# STM32.net
KiCad netlist of a schematic drawn in Altium Designer
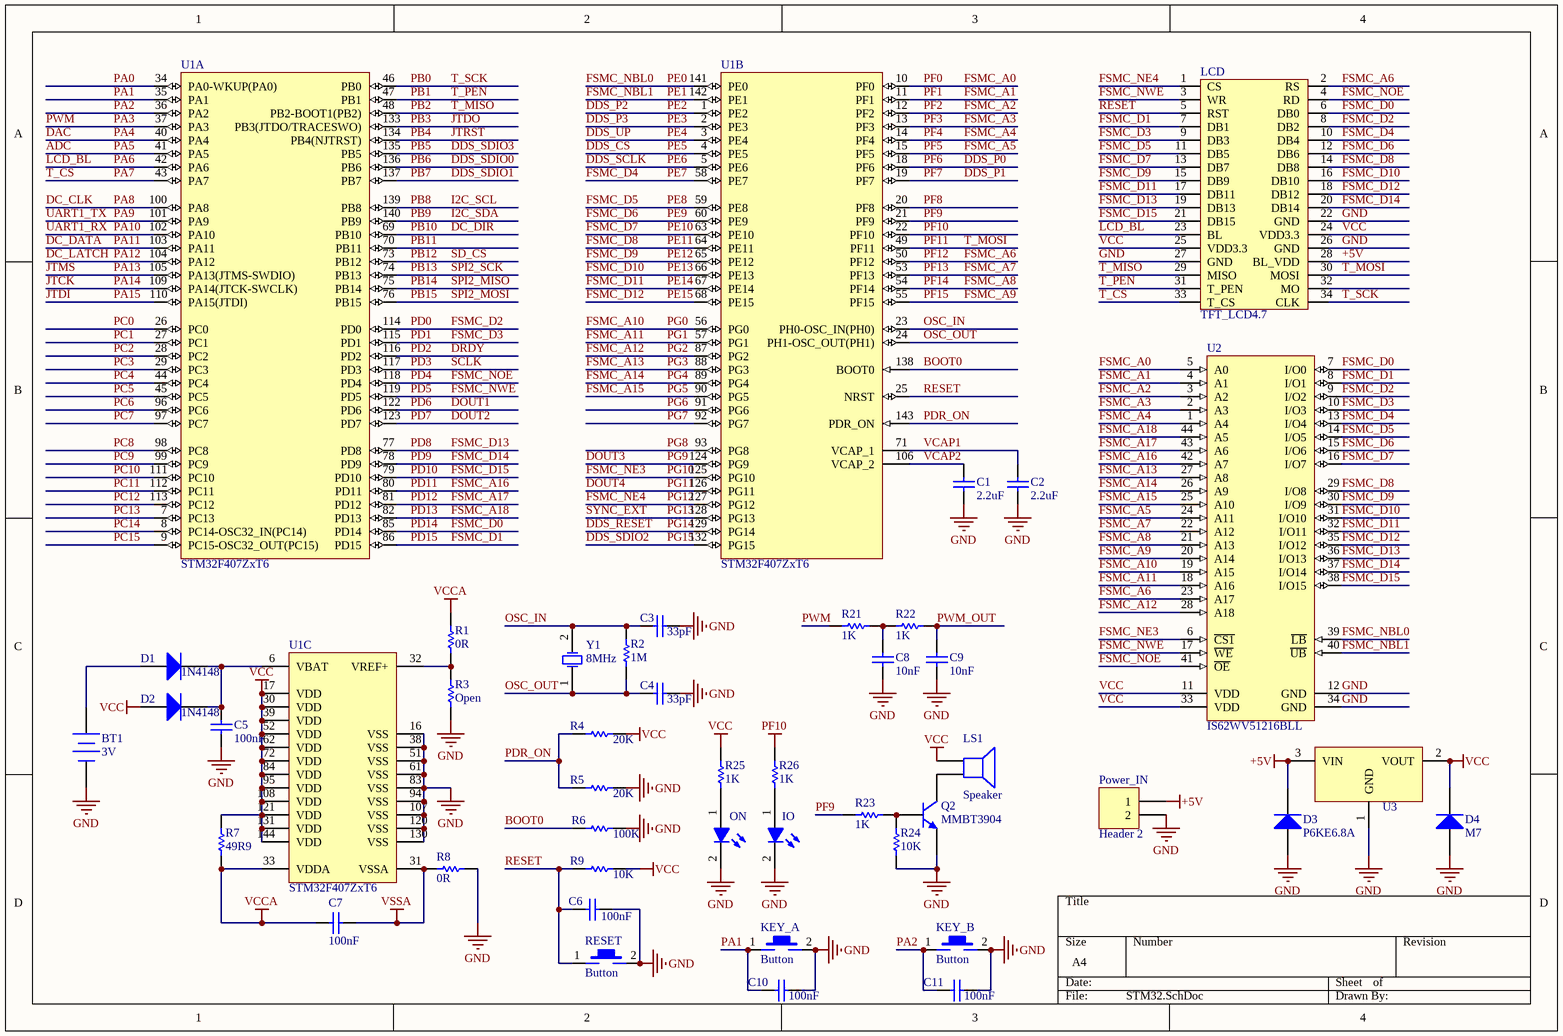
[diagram p0: STM32.SchDoc]

(export (version "E")
  (design (tool "Eeschema 10.0.6"))
  (components
    (comp (ref "BT1")
      (value "3V")
      (footprint "BAT-2")
      (description "Multicell Battery")
      (fields (field (name "PUBLISHER") "Altium Limited"))
      (libsource (lib "Miscellaneous Devices") (part "Battery"))
    )
    (comp (ref "C1")
      (value "2.2uF")
      (footprint "CAPC0603(1608)55_M")
      (libsource (lib "Slivy's ibrary") (part "CAP"))
    )
    (comp (ref "C2")
      (value "2.2uF")
      (footprint "CAPC0603(1608)55_M")
      (libsource (lib "Slivy's ibrary") (part "CAP"))
    )
    (comp (ref "C3")
      (value "33pF")
      (footprint "CAPC0603(1608)55_M")
      (libsource (lib "Slivy's ibrary") (part "CAP"))
    )
    (comp (ref "C4")
      (value "33pF")
      (footprint "CAPC0603(1608)55_M")
      (libsource (lib "Slivy's ibrary") (part "CAP"))
    )
    (comp (ref "C5")
      (value "100nF")
      (footprint "CAPC0603(1608)55_M")
      (libsource (lib "Slivy's ibrary") (part "CAP"))
    )
    (comp (ref "C6")
      (value "100nF")
      (footprint "CAPC0603(1608)55_M")
      (libsource (lib "Slivy's ibrary") (part "CAP"))
    )
    (comp (ref "C7")
      (value "100nF")
      (footprint "CAPC0603(1608)55_M")
      (libsource (lib "Slivy's ibrary") (part "CAP"))
    )
    (comp (ref "C8")
      (value "10nF")
      (footprint "CAPC0603(1608)55_M")
      (libsource (lib "Slivy's ibrary") (part "CAP"))
    )
    (comp (ref "C9")
      (value "10nF")
      (footprint "CAPC0603(1608)55_M")
      (libsource (lib "Slivy's ibrary") (part "CAP"))
    )
    (comp (ref "C10")
      (value "100nF")
      (footprint "CAPC0603(1608)55_M")
      (libsource (lib "Slivy's ibrary") (part "CAP"))
    )
    (comp (ref "C11")
      (value "100nF")
      (footprint "CAPC0603(1608)55_M")
      (libsource (lib "Slivy's ibrary") (part "CAP"))
    )
    (comp (ref "D1") (value "1N4148") (footprint "LL34") (libsource (lib "Slivy's ibrary") (part "Diode")))
    (comp (ref "D2") (value "1N4148") (footprint "LL34") (libsource (lib "Slivy's ibrary") (part "Diode")))
    (comp (ref "D3")
      (value "P6KE6.8A")
      (footprint "DO-214AC")
      (libsource (lib "Slivy's ibrary") (part "Diode"))
    )
    (comp (ref "D4") (value "M7") (footprint "DO-214AC") (libsource (lib "Slivy's ibrary") (part "Diode")))
    (comp (ref "IO")
      (value "LED-BLUE")
      (footprint "0603LED_BLUE_V")
      (libsource (lib "Slivy's ibrary") (part "LED-BLUE"))
    )
    (comp (ref "KEY_A")
      (value "Button")
      (footprint "Button665")
      (libsource (lib "Slivy's ibrary") (part "Button"))
    )
    (comp (ref "KEY_B")
      (value "Button")
      (footprint "Button665")
      (libsource (lib "Slivy's ibrary") (part "Button"))
    )
    (comp (ref "LCD")
      (value "TFT_LCD4.7")
      (footprint "DB2*17-3.5")
      (libsource (lib "Slivy's ibrary") (part "TFT_LCD4.7"))
    )
    (comp (ref "LS1")
      (value "Speaker")
      (footprint "Buzzer")
      (description "Loudspeaker")
      (fields (field (name "PUBLISHER") "Altium Limited"))
      (libsource (lib "Miscellaneous Devices") (part "Speaker"))
    )
    (comp (ref "ON")
      (value "LED-BLUE")
      (footprint "0603LED_BLUE_V")
      (libsource (lib "Slivy's ibrary") (part "LED-BLUE"))
    )
    (comp (ref "Power_IN")
      (value "Header 2")
      (footprint "VH3.96-2-AW")
      (description "Header, 2-Pin")
      (fields (field (name "PUBLISHER") "Altium Limited"))
      (libsource (lib "Miscellaneous Connectors") (part "Header 2"))
    )
    (comp (ref "Q2")
      (value "MMBT3904")
      (footprint "SOT23_M")
      (description "NPN General Purpose Amplifier")
      (fields (field (name "PUBLISHER") "Altium Limited"))
      (libsource (lib "Slivy's ibrary") (part "MMBT3904"))
    )
    (comp (ref "R1")
      (value "0R")
      (footprint "RESC0603(1608)_M")
      (libsource (lib "Slivy's ibrary") (part "RES"))
    )
    (comp (ref "R2")
      (value "1M")
      (footprint "RESC0603(1608)_M")
      (libsource (lib "Slivy's ibrary") (part "RES"))
    )
    (comp (ref "R3")
      (value "Open")
      (footprint "RESC0603(1608)_M")
      (libsource (lib "Slivy's ibrary") (part "RES"))
    )
    (comp (ref "R4")
      (value "20K")
      (footprint "RESC0603(1608)_M")
      (libsource (lib "Slivy's ibrary") (part "RES"))
    )
    (comp (ref "R5")
      (value "20K")
      (footprint "RESC0603(1608)_M")
      (libsource (lib "Slivy's ibrary") (part "RES"))
    )
    (comp (ref "R6")
      (value "100K")
      (footprint "RESC0603(1608)_M")
      (libsource (lib "Slivy's ibrary") (part "RES"))
    )
    (comp (ref "R7")
      (value "49R9")
      (footprint "RESC0603(1608)_M")
      (libsource (lib "Slivy's ibrary") (part "RES"))
    )
    (comp (ref "R8")
      (value "0R")
      (footprint "RESC0603(1608)_M")
      (libsource (lib "Slivy's ibrary") (part "RES"))
    )
    (comp (ref "R9")
      (value "10K")
      (footprint "RESC0603(1608)_M")
      (libsource (lib "Slivy's ibrary") (part "RES"))
    )
    (comp (ref "R21")
      (value "1K")
      (footprint "RESC0603(1608)_M")
      (libsource (lib "Slivy's ibrary") (part "RES"))
    )
    (comp (ref "R22")
      (value "1K")
      (footprint "RESC0603(1608)_M")
      (libsource (lib "Slivy's ibrary") (part "RES"))
    )
    (comp (ref "R23")
      (value "1K")
      (footprint "RESC0603(1608)_M")
      (libsource (lib "Slivy's ibrary") (part "RES"))
    )
    (comp (ref "R24")
      (value "10K")
      (footprint "RESC0603(1608)_M")
      (libsource (lib "Slivy's ibrary") (part "RES"))
    )
    (comp (ref "R25")
      (value "1K")
      (footprint "RESC0603(1608)_M")
      (libsource (lib "Slivy's ibrary") (part "RES"))
    )
    (comp (ref "R26")
      (value "1K")
      (footprint "RESC0603(1608)_M")
      (libsource (lib "Slivy's ibrary") (part "RES"))
    )
    (comp (ref "RESET")
      (value "Button")
      (footprint "Button665")
      (libsource (lib "Slivy's ibrary") (part "Button"))
    )
    (comp (ref "U1")
      (value "STM32F407ZxT6")
      (footprint "LQFP144")
      (libsource (lib "Slivy's ibrary") (part "STM32F407ZxT6"))
    )
    (comp (ref "U2")
      (value "IS62WV51216BLL")
      (footprint "TSOP-2-44")
      (libsource (lib "Slivy's ibrary") (part "IS62WV51216BLL"))
    )
    (comp (ref "U3")
      (value "AMS1117")
      (footprint "SOT-223_M")
      (libsource (lib "Slivy's ibrary") (part "AMS1117"))
    )
    (comp (ref "Y1")
      (value "8MHz")
      (footprint "HC-49S")
      (description "Crystal Oscillator")
      (fields (field (name "PUBLISHER") "Altium Limited"))
      (libsource (lib "Slivy's ibrary") (part "XTAL"))
    )
  )
  (nets
    (net (code "1") (name "+5V") (class "Default")
      (node (ref "D3") (pin "1") (pinfunction "K_1") (pintype "passive"))
      (node (ref "LCD") (pin "28") (pinfunction "BL_VDD_28") (pintype "passive"))
      (node (ref "Power_IN") (pin "1") (pinfunction "1_1") (pintype "passive"))
      (node (ref "U3") (pin "3") (pinfunction "VIN_3") (pintype "power_in"))
    )
    (net (code "2") (name "/ADC") (class "Default")
      (node (ref "U1") (pin "41") (pinfunction "PA5_41") (pintype "bidirectional"))
    )
    (net (code "3") (name "/BOOT0") (class "Default")
      (node (ref "R6") (pin "1") (pinfunction "1_1") (pintype "passive"))
      (node (ref "U1") (pin "138") (pinfunction "BOOT0_138") (pintype "input"))
    )
    (net (code "4") (name "/DAC") (class "Default")
      (node (ref "U1") (pin "40") (pinfunction "PA4_40") (pintype "bidirectional"))
    )
    (net (code "5") (name "/DC_CLK") (class "Default")
      (node (ref "U1") (pin "100") (pinfunction "PA8_100") (pintype "bidirectional"))
    )
    (net (code "6") (name "/DC_DATA") (class "Default")
      (node (ref "U1") (pin "103") (pinfunction "PA11_103") (pintype "bidirectional"))
    )
    (net (code "7") (name "/DC_DIR") (class "Default")
      (node (ref "U1") (pin "69") (pinfunction "PB10_69") (pintype "bidirectional"))
    )
    (net (code "8") (name "/DC_LATCH") (class "Default")
      (node (ref "U1") (pin "104") (pinfunction "PA12_104") (pintype "bidirectional"))
    )
    (net (code "9") (name "/DDS_CS") (class "Default")
      (node (ref "U1") (pin "4") (pinfunction "PE5_4") (pintype "bidirectional"))
    )
    (net (code "10") (name "/DDS_P0") (class "Default")
      (node (ref "U1") (pin "18") (pinfunction "PF6_18") (pintype "bidirectional"))
    )
    (net (code "11") (name "/DDS_P1") (class "Default")
      (node (ref "U1") (pin "19") (pinfunction "PF7_19") (pintype "bidirectional"))
    )
    (net (code "12") (name "/DDS_P2") (class "Default")
      (node (ref "U1") (pin "1") (pinfunction "PE2_1") (pintype "bidirectional"))
    )
    (net (code "13") (name "/DDS_P3") (class "Default")
      (node (ref "U1") (pin "2") (pinfunction "PE3_2") (pintype "bidirectional"))
    )
    (net (code "14") (name "/DDS_RESET") (class "Default")
      (node (ref "U1") (pin "129") (pinfunction "PG14_129") (pintype "bidirectional"))
    )
    (net (code "15") (name "/DDS_SCLK") (class "Default")
      (node (ref "U1") (pin "5") (pinfunction "PE6_5") (pintype "bidirectional"))
    )
    (net (code "16") (name "/DDS_SDIO0") (class "Default")
      (node (ref "U1") (pin "136") (pinfunction "PB6_136") (pintype "bidirectional"))
    )
    (net (code "17") (name "/DDS_SDIO1") (class "Default")
      (node (ref "U1") (pin "137") (pinfunction "PB7_137") (pintype "bidirectional"))
    )
    (net (code "18") (name "/DDS_SDIO2") (class "Default")
      (node (ref "U1") (pin "132") (pinfunction "PG15_132") (pintype "bidirectional"))
    )
    (net (code "19") (name "/DDS_SDIO3") (class "Default")
      (node (ref "U1") (pin "135") (pinfunction "PB5_135") (pintype "bidirectional"))
    )
    (net (code "20") (name "/DDS_UP") (class "Default")
      (node (ref "U1") (pin "3") (pinfunction "PE4_3") (pintype "bidirectional"))
    )
    (net (code "21") (name "/DOUT1") (class "Default")
      (node (ref "U1") (pin "122") (pinfunction "PD6_122") (pintype "bidirectional"))
    )
    (net (code "22") (name "/DOUT2") (class "Default")
      (node (ref "U1") (pin "123") (pinfunction "PD7_123") (pintype "bidirectional"))
    )
    (net (code "23") (name "/DOUT3") (class "Default")
      (node (ref "U1") (pin "124") (pinfunction "PG9_124") (pintype "bidirectional"))
    )
    (net (code "24") (name "/DOUT4") (class "Default")
      (node (ref "U1") (pin "126") (pinfunction "PG11_126") (pintype "bidirectional"))
    )
    (net (code "25") (name "/DRDY") (class "Default")
      (node (ref "U1") (pin "116") (pinfunction "PD2_116") (pintype "bidirectional"))
    )
    (net (code "26") (name "/FSMC_A0") (class "Default")
      (node (ref "U1") (pin "10") (pinfunction "PF0_10") (pintype "bidirectional"))
      (node (ref "U2") (pin "5") (pinfunction "A0_5") (pintype "input"))
    )
    (net (code "27") (name "/FSMC_A1") (class "Default")
      (node (ref "U1") (pin "11") (pinfunction "PF1_11") (pintype "bidirectional"))
      (node (ref "U2") (pin "4") (pinfunction "A1_4") (pintype "input"))
    )
    (net (code "28") (name "/FSMC_A2") (class "Default")
      (node (ref "U1") (pin "12") (pinfunction "PF2_12") (pintype "bidirectional"))
      (node (ref "U2") (pin "3") (pinfunction "A2_3") (pintype "input"))
    )
    (net (code "29") (name "/FSMC_A3") (class "Default")
      (node (ref "U1") (pin "13") (pinfunction "PF3_13") (pintype "bidirectional"))
      (node (ref "U2") (pin "2") (pinfunction "A3_2") (pintype "input"))
    )
    (net (code "30") (name "/FSMC_A4") (class "Default")
      (node (ref "U1") (pin "14") (pinfunction "PF4_14") (pintype "bidirectional"))
      (node (ref "U2") (pin "1") (pinfunction "A4_1") (pintype "input"))
    )
    (net (code "31") (name "/FSMC_A5") (class "Default")
      (node (ref "U1") (pin "15") (pinfunction "PF5_15") (pintype "bidirectional"))
      (node (ref "U2") (pin "24") (pinfunction "A11_24") (pintype "input"))
    )
    (net (code "32") (name "/FSMC_A6") (class "Default")
      (node (ref "LCD") (pin "2") (pinfunction "RS_2") (pintype "passive"))
      (node (ref "U1") (pin "50") (pinfunction "PF12_50") (pintype "bidirectional"))
      (node (ref "U2") (pin "23") (pinfunction "A17_23") (pintype "input"))
    )
    (net (code "33") (name "/FSMC_A7") (class "Default")
      (node (ref "U1") (pin "53") (pinfunction "PF13_53") (pintype "bidirectional"))
      (node (ref "U2") (pin "22") (pinfunction "A12_22") (pintype "input"))
    )
    (net (code "34") (name "/FSMC_A8") (class "Default")
      (node (ref "U1") (pin "54") (pinfunction "PF14_54") (pintype "bidirectional"))
      (node (ref "U2") (pin "21") (pinfunction "A13_21") (pintype "input"))
    )
    (net (code "35") (name "/FSMC_A9") (class "Default")
      (node (ref "U1") (pin "55") (pinfunction "PF15_55") (pintype "bidirectional"))
      (node (ref "U2") (pin "20") (pinfunction "A14_20") (pintype "input"))
    )
    (net (code "36") (name "/FSMC_A10") (class "Default")
      (node (ref "U1") (pin "56") (pinfunction "PG0_56") (pintype "bidirectional"))
      (node (ref "U2") (pin "19") (pinfunction "A15_19") (pintype "input"))
    )
    (net (code "37") (name "/FSMC_A11") (class "Default")
      (node (ref "U1") (pin "57") (pinfunction "PG1_57") (pintype "bidirectional"))
      (node (ref "U2") (pin "18") (pinfunction "A16_18") (pintype "input"))
    )
    (net (code "38") (name "/FSMC_A12") (class "Default")
      (node (ref "U1") (pin "87") (pinfunction "PG2_87") (pintype "bidirectional"))
      (node (ref "U2") (pin "28") (pinfunction "A18_28") (pintype "input"))
    )
    (net (code "39") (name "/FSMC_A13") (class "Default")
      (node (ref "U1") (pin "88") (pinfunction "PG3_88") (pintype "bidirectional"))
      (node (ref "U2") (pin "27") (pinfunction "A8_27") (pintype "input"))
    )
    (net (code "40") (name "/FSMC_A14") (class "Default")
      (node (ref "U1") (pin "89") (pinfunction "PG4_89") (pintype "bidirectional"))
      (node (ref "U2") (pin "26") (pinfunction "A9_26") (pintype "input"))
    )
    (net (code "41") (name "/FSMC_A15") (class "Default")
      (node (ref "U1") (pin "90") (pinfunction "PG5_90") (pintype "bidirectional"))
      (node (ref "U2") (pin "25") (pinfunction "A10_25") (pintype "input"))
    )
    (net (code "42") (name "/FSMC_A16") (class "Default")
      (node (ref "U1") (pin "80") (pinfunction "PD11_80") (pintype "bidirectional"))
      (node (ref "U2") (pin "42") (pinfunction "A7_42") (pintype "input"))
    )
    (net (code "43") (name "/FSMC_A17") (class "Default")
      (node (ref "U1") (pin "81") (pinfunction "PD12_81") (pintype "bidirectional"))
      (node (ref "U2") (pin "43") (pinfunction "A6_43") (pintype "input"))
    )
    (net (code "44") (name "/FSMC_A18") (class "Default")
      (node (ref "U1") (pin "82") (pinfunction "PD13_82") (pintype "bidirectional"))
      (node (ref "U2") (pin "44") (pinfunction "A5_44") (pintype "input"))
    )
    (net (code "45") (name "/FSMC_D0") (class "Default")
      (node (ref "LCD") (pin "6") (pinfunction "DB0_6") (pintype "passive"))
      (node (ref "U1") (pin "85") (pinfunction "PD14_85") (pintype "bidirectional"))
      (node (ref "U2") (pin "7") (pinfunction "I/O0_7") (pintype "bidirectional"))
    )
    (net (code "46") (name "/FSMC_D1") (class "Default")
      (node (ref "LCD") (pin "7") (pinfunction "DB1_7") (pintype "passive"))
      (node (ref "U1") (pin "86") (pinfunction "PD15_86") (pintype "bidirectional"))
      (node (ref "U2") (pin "8") (pinfunction "I/O1_8") (pintype "bidirectional"))
    )
    (net (code "47") (name "/FSMC_D2") (class "Default")
      (node (ref "LCD") (pin "8") (pinfunction "DB2_8") (pintype "passive"))
      (node (ref "U1") (pin "114") (pinfunction "PD0_114") (pintype "bidirectional"))
      (node (ref "U2") (pin "9") (pinfunction "I/O2_9") (pintype "bidirectional"))
    )
    (net (code "48") (name "/FSMC_D3") (class "Default")
      (node (ref "LCD") (pin "9") (pinfunction "DB3_9") (pintype "passive"))
      (node (ref "U1") (pin "115") (pinfunction "PD1_115") (pintype "bidirectional"))
      (node (ref "U2") (pin "10") (pinfunction "I/O3_10") (pintype "bidirectional"))
    )
    (net (code "49") (name "/FSMC_D4") (class "Default")
      (node (ref "LCD") (pin "10") (pinfunction "DB4_10") (pintype "passive"))
      (node (ref "U1") (pin "58") (pinfunction "PE7_58") (pintype "bidirectional"))
      (node (ref "U2") (pin "13") (pinfunction "I/O4_13") (pintype "bidirectional"))
    )
    (net (code "50") (name "/FSMC_D5") (class "Default")
      (node (ref "LCD") (pin "11") (pinfunction "DB5_11") (pintype "passive"))
      (node (ref "U1") (pin "59") (pinfunction "PE8_59") (pintype "bidirectional"))
      (node (ref "U2") (pin "14") (pinfunction "I/O5_14") (pintype "bidirectional"))
    )
    (net (code "51") (name "/FSMC_D6") (class "Default")
      (node (ref "LCD") (pin "12") (pinfunction "DB6_12") (pintype "passive"))
      (node (ref "U1") (pin "60") (pinfunction "PE9_60") (pintype "bidirectional"))
      (node (ref "U2") (pin "15") (pinfunction "I/O6_15") (pintype "bidirectional"))
    )
    (net (code "52") (name "/FSMC_D7") (class "Default")
      (node (ref "LCD") (pin "13") (pinfunction "DB7_13") (pintype "passive"))
      (node (ref "U1") (pin "63") (pinfunction "PE10_63") (pintype "bidirectional"))
      (node (ref "U2") (pin "16") (pinfunction "I/O7_16") (pintype "bidirectional"))
    )
    (net (code "53") (name "/FSMC_D8") (class "Default")
      (node (ref "LCD") (pin "14") (pinfunction "DB8_14") (pintype "passive"))
      (node (ref "U1") (pin "64") (pinfunction "PE11_64") (pintype "bidirectional"))
      (node (ref "U2") (pin "29") (pinfunction "I/O8_29") (pintype "bidirectional"))
    )
    (net (code "54") (name "/FSMC_D9") (class "Default")
      (node (ref "LCD") (pin "15") (pinfunction "DB9_15") (pintype "passive"))
      (node (ref "U1") (pin "65") (pinfunction "PE12_65") (pintype "bidirectional"))
      (node (ref "U2") (pin "30") (pinfunction "I/O9_30") (pintype "bidirectional"))
    )
    (net (code "55") (name "/FSMC_D10") (class "Default")
      (node (ref "LCD") (pin "16") (pinfunction "DB10_16") (pintype "passive"))
      (node (ref "U1") (pin "66") (pinfunction "PE13_66") (pintype "bidirectional"))
      (node (ref "U2") (pin "31") (pinfunction "I/O10_31") (pintype "bidirectional"))
    )
    (net (code "56") (name "/FSMC_D11") (class "Default")
      (node (ref "LCD") (pin "17") (pinfunction "DB11_17") (pintype "passive"))
      (node (ref "U1") (pin "67") (pinfunction "PE14_67") (pintype "bidirectional"))
      (node (ref "U2") (pin "32") (pinfunction "I/O11_32") (pintype "bidirectional"))
    )
    (net (code "57") (name "/FSMC_D12") (class "Default")
      (node (ref "LCD") (pin "18") (pinfunction "DB12_18") (pintype "passive"))
      (node (ref "U1") (pin "68") (pinfunction "PE15_68") (pintype "bidirectional"))
      (node (ref "U2") (pin "35") (pinfunction "I/O12_35") (pintype "bidirectional"))
    )
    (net (code "58") (name "/FSMC_D13") (class "Default")
      (node (ref "LCD") (pin "19") (pinfunction "DB13_19") (pintype "passive"))
      (node (ref "U1") (pin "77") (pinfunction "PD8_77") (pintype "bidirectional"))
      (node (ref "U2") (pin "36") (pinfunction "I/O13_36") (pintype "bidirectional"))
    )
    (net (code "59") (name "/FSMC_D14") (class "Default")
      (node (ref "LCD") (pin "20") (pinfunction "DB14_20") (pintype "passive"))
      (node (ref "U1") (pin "78") (pinfunction "PD9_78") (pintype "bidirectional"))
      (node (ref "U2") (pin "37") (pinfunction "I/O14_37") (pintype "bidirectional"))
    )
    (net (code "60") (name "/FSMC_D15") (class "Default")
      (node (ref "LCD") (pin "21") (pinfunction "DB15_21") (pintype "passive"))
      (node (ref "U1") (pin "79") (pinfunction "PD10_79") (pintype "bidirectional"))
      (node (ref "U2") (pin "38") (pinfunction "I/O15_38") (pintype "bidirectional"))
    )
    (net (code "61") (name "/FSMC_NBL0") (class "Default")
      (node (ref "U1") (pin "141") (pinfunction "PE0_141") (pintype "bidirectional"))
      (node (ref "U2") (pin "39") (pinfunction "~{LB}_39") (pintype "input"))
    )
    (net (code "62") (name "/FSMC_NBL1") (class "Default")
      (node (ref "U1") (pin "142") (pinfunction "PE1_142") (pintype "bidirectional"))
      (node (ref "U2") (pin "40") (pinfunction "~{UB}_40") (pintype "input"))
    )
    (net (code "63") (name "/FSMC_NE3") (class "Default")
      (node (ref "U1") (pin "125") (pinfunction "PG10_125") (pintype "bidirectional"))
      (node (ref "U2") (pin "6") (pinfunction "~{CS1}_6") (pintype "input"))
    )
    (net (code "64") (name "/FSMC_NE4") (class "Default")
      (node (ref "LCD") (pin "1") (pinfunction "CS_1") (pintype "passive"))
      (node (ref "U1") (pin "127") (pinfunction "PG12_127") (pintype "bidirectional"))
    )
    (net (code "65") (name "/FSMC_NOE") (class "Default")
      (node (ref "LCD") (pin "4") (pinfunction "RD_4") (pintype "passive"))
      (node (ref "U1") (pin "118") (pinfunction "PD4_118") (pintype "bidirectional"))
      (node (ref "U2") (pin "41") (pinfunction "~{OE}_41") (pintype "input"))
    )
    (net (code "66") (name "/FSMC_NWE") (class "Default")
      (node (ref "LCD") (pin "3") (pinfunction "WR_3") (pintype "passive"))
      (node (ref "U1") (pin "119") (pinfunction "PD5_119") (pintype "bidirectional"))
      (node (ref "U2") (pin "17") (pinfunction "~{WE}_17") (pintype "input"))
    )
    (net (code "67") (name "/I2C_SCL") (class "Default")
      (node (ref "U1") (pin "139") (pinfunction "PB8_139") (pintype "bidirectional"))
    )
    (net (code "68") (name "/I2C_SDA") (class "Default")
      (node (ref "U1") (pin "140") (pinfunction "PB9_140") (pintype "bidirectional"))
    )
    (net (code "69") (name "/JTCK") (class "Default")
      (node (ref "U1") (pin "109") (pinfunction "PA14(JTCK-SWCLK)_109") (pintype "bidirectional"))
    )
    (net (code "70") (name "/JTDI") (class "Default")
      (node (ref "U1") (pin "110") (pinfunction "PA15(JTDI)_110") (pintype "bidirectional"))
    )
    (net (code "71") (name "/JTDO") (class "Default")
      (node (ref "U1") (pin "133") (pinfunction "PB3(JTDO/TRACESWO)_133") (pintype "bidirectional"))
    )
    (net (code "72") (name "/JTMS") (class "Default")
      (node (ref "U1") (pin "105") (pinfunction "PA13(JTMS-SWDIO)_105") (pintype "bidirectional"))
    )
    (net (code "73") (name "/JTRST") (class "Default")
      (node (ref "U1") (pin "134") (pinfunction "PB4(NJTRST)_134") (pintype "bidirectional"))
    )
    (net (code "74") (name "/LCD_BL") (class "Default")
      (node (ref "LCD") (pin "23") (pinfunction "BL_23") (pintype "passive"))
      (node (ref "U1") (pin "42") (pinfunction "PA6_42") (pintype "bidirectional"))
    )
    (net (code "75") (name "/OSC_IN") (class "Default")
      (node (ref "C3") (pin "1") (pinfunction "1_1") (pintype "passive"))
      (node (ref "R2") (pin "2") (pinfunction "2_2") (pintype "passive"))
      (node (ref "U1") (pin "23") (pinfunction "PH0-OSC_IN(PH0)_23") (pintype "bidirectional"))
      (node (ref "Y1") (pin "2") (pinfunction "OSC2_2") (pintype "passive"))
    )
    (net (code "76") (name "/OSC_OUT") (class "Default")
      (node (ref "C4") (pin "1") (pinfunction "1_1") (pintype "passive"))
      (node (ref "R2") (pin "1") (pinfunction "1_1") (pintype "passive"))
      (node (ref "U1") (pin "24") (pinfunction "PH1-OSC_OUT(PH1)_24") (pintype "bidirectional"))
      (node (ref "Y1") (pin "1") (pinfunction "OSC1_1") (pintype "passive"))
    )
    (net (code "77") (name "/PA0") (class "Default")
      (node (ref "U1") (pin "34") (pinfunction "PA0-WKUP(PA0)_34") (pintype "bidirectional"))
    )
    (net (code "78") (name "/PA1") (class "Default")
      (node (ref "C10") (pin "1") (pinfunction "1_1") (pintype "passive"))
      (node (ref "KEY_A") (pin "1") (pinfunction "1_1") (pintype "passive"))
      (node (ref "U1") (pin "35") (pinfunction "PA1_35") (pintype "bidirectional"))
    )
    (net (code "79") (name "/PA2") (class "Default")
      (node (ref "C11") (pin "1") (pinfunction "1_1") (pintype "passive"))
      (node (ref "KEY_B") (pin "1") (pinfunction "1_1") (pintype "passive"))
      (node (ref "U1") (pin "36") (pinfunction "PA2_36") (pintype "bidirectional"))
    )
    (net (code "80") (name "/PA3") (class "Default")
      (node (ref "R21") (pin "1") (pinfunction "1_1") (pintype "passive"))
      (node (ref "U1") (pin "37") (pinfunction "PA3_37") (pintype "bidirectional"))
    )
    (net (code "81") (name "/PA7") (class "Default")
      (node (ref "LCD") (pin "33") (pinfunction "T_CS_33") (pintype "passive"))
      (node (ref "U1") (pin "43") (pinfunction "PA7_43") (pintype "bidirectional"))
    )
    (net (code "82") (name "/PA9") (class "Default")
      (node (ref "U1") (pin "101") (pinfunction "PA9_101") (pintype "bidirectional"))
    )
    (net (code "83") (name "/PA10") (class "Default")
      (node (ref "U1") (pin "102") (pinfunction "PA10_102") (pintype "bidirectional"))
    )
    (net (code "84") (name "/PB0") (class "Default")
      (node (ref "LCD") (pin "34") (pinfunction "CLK_34") (pintype "passive"))
      (node (ref "U1") (pin "46") (pinfunction "PB0_46") (pintype "bidirectional"))
    )
    (net (code "85") (name "/PB1") (class "Default")
      (node (ref "LCD") (pin "31") (pinfunction "T_PEN_31") (pintype "passive"))
      (node (ref "U1") (pin "47") (pinfunction "PB1_47") (pintype "bidirectional"))
    )
    (net (code "86") (name "/PB2") (class "Default")
      (node (ref "LCD") (pin "29") (pinfunction "MISO_29") (pintype "passive"))
      (node (ref "U1") (pin "48") (pinfunction "PB2-BOOT1(PB2)_48") (pintype "bidirectional"))
    )
    (net (code "87") (name "/PB11") (class "Default")
      (node (ref "U1") (pin "70") (pinfunction "PB11_70") (pintype "bidirectional"))
    )
    (net (code "88") (name "/PB12") (class "Default")
      (node (ref "U1") (pin "73") (pinfunction "PB12_73") (pintype "bidirectional"))
    )
    (net (code "89") (name "/PB13") (class "Default")
      (node (ref "U1") (pin "74") (pinfunction "PB13_74") (pintype "bidirectional"))
    )
    (net (code "90") (name "/PB14") (class "Default")
      (node (ref "U1") (pin "75") (pinfunction "PB14_75") (pintype "bidirectional"))
    )
    (net (code "91") (name "/PB15") (class "Default")
      (node (ref "U1") (pin "76") (pinfunction "PB15_76") (pintype "bidirectional"))
    )
    (net (code "92") (name "/PC0") (class "Default")
      (node (ref "U1") (pin "26") (pinfunction "PC0_26") (pintype "bidirectional"))
    )
    (net (code "93") (name "/PC1") (class "Default")
      (node (ref "U1") (pin "27") (pinfunction "PC1_27") (pintype "bidirectional"))
    )
    (net (code "94") (name "/PC2") (class "Default")
      (node (ref "U1") (pin "28") (pinfunction "PC2_28") (pintype "bidirectional"))
    )
    (net (code "95") (name "/PC3") (class "Default")
      (node (ref "U1") (pin "29") (pinfunction "PC3_29") (pintype "bidirectional"))
    )
    (net (code "96") (name "/PC4") (class "Default")
      (node (ref "U1") (pin "44") (pinfunction "PC4_44") (pintype "bidirectional"))
    )
    (net (code "97") (name "/PC5") (class "Default")
      (node (ref "U1") (pin "45") (pinfunction "PC5_45") (pintype "bidirectional"))
    )
    (net (code "98") (name "/PC6") (class "Default")
      (node (ref "U1") (pin "96") (pinfunction "PC6_96") (pintype "bidirectional"))
    )
    (net (code "99") (name "/PC7") (class "Default")
      (node (ref "U1") (pin "97") (pinfunction "PC7_97") (pintype "bidirectional"))
    )
    (net (code "100") (name "/PC8") (class "Default")
      (node (ref "U1") (pin "98") (pinfunction "PC8_98") (pintype "bidirectional"))
    )
    (net (code "101") (name "/PC9") (class "Default")
      (node (ref "U1") (pin "99") (pinfunction "PC9_99") (pintype "bidirectional"))
    )
    (net (code "102") (name "/PC10") (class "Default")
      (node (ref "U1") (pin "111") (pinfunction "PC10_111") (pintype "bidirectional"))
    )
    (net (code "103") (name "/PC11") (class "Default")
      (node (ref "U1") (pin "112") (pinfunction "PC11_112") (pintype "bidirectional"))
    )
    (net (code "104") (name "/PC12") (class "Default")
      (node (ref "U1") (pin "113") (pinfunction "PC12_113") (pintype "bidirectional"))
    )
    (net (code "105") (name "/PC13") (class "Default")
      (node (ref "U1") (pin "7") (pinfunction "PC13_7") (pintype "bidirectional"))
    )
    (net (code "106") (name "/PC14") (class "Default")
      (node (ref "U1") (pin "8") (pinfunction "PC14-OSC32_IN(PC14)_8") (pintype "bidirectional"))
    )
    (net (code "107") (name "/PC15") (class "Default")
      (node (ref "U1") (pin "9") (pinfunction "PC15-OSC32_OUT(PC15)_9") (pintype "bidirectional"))
    )
    (net (code "108") (name "/PD3") (class "Default")
      (node (ref "U1") (pin "117") (pinfunction "PD3_117") (pintype "bidirectional"))
    )
    (net (code "109") (name "/PDR_ON") (class "Default")
      (node (ref "R4") (pin "2") (pinfunction "2_2") (pintype "passive"))
      (node (ref "R5") (pin "2") (pinfunction "2_2") (pintype "passive"))
      (node (ref "U1") (pin "143") (pinfunction "PDR_ON_143") (pintype "input"))
    )
    (net (code "110") (name "/PF8") (class "Default")
      (node (ref "U1") (pin "20") (pinfunction "PF8_20") (pintype "bidirectional"))
    )
    (net (code "111") (name "/PF9") (class "Default")
      (node (ref "R23") (pin "1") (pinfunction "1_1") (pintype "passive"))
      (node (ref "U1") (pin "21") (pinfunction "PF9_21") (pintype "bidirectional"))
    )
    (net (code "112") (name "/PF11") (class "Default")
      (node (ref "LCD") (pin "30") (pinfunction "MOSI_30") (pintype "passive"))
      (node (ref "U1") (pin "49") (pinfunction "PF11_49") (pintype "bidirectional"))
    )
    (net (code "113") (name "/PG6") (class "Default")
      (node (ref "U1") (pin "91") (pinfunction "PG6_91") (pintype "bidirectional"))
    )
    (net (code "114") (name "/PG7") (class "Default")
      (node (ref "U1") (pin "92") (pinfunction "PG7_92") (pintype "bidirectional"))
    )
    (net (code "115") (name "/PG8") (class "Default")
      (node (ref "U1") (pin "93") (pinfunction "PG8_93") (pintype "bidirectional"))
    )
    (net (code "116") (name "/PG13") (class "Default")
      (node (ref "U1") (pin "128") (pinfunction "PG13_128") (pintype "bidirectional"))
    )
    (net (code "117") (name "/PWM_OUT") (class "Default")
      (node (ref "C9") (pin "2") (pinfunction "2_2") (pintype "passive"))
      (node (ref "R22") (pin "2") (pinfunction "2_2") (pintype "passive"))
    )
    (net (code "118") (name "/RESET") (class "Default")
      (node (ref "C6") (pin "1") (pinfunction "1_1") (pintype "passive"))
      (node (ref "LCD") (pin "5") (pinfunction "RST_5") (pintype "passive"))
      (node (ref "R9") (pin "1") (pinfunction "1_1") (pintype "passive"))
      (node (ref "RESET") (pin "1") (pinfunction "1_1") (pintype "passive"))
      (node (ref "U1") (pin "25") (pinfunction "NRST_25") (pintype "bidirectional"))
    )
    (net (code "119") (name "/VCAP1") (class "Default")
      (node (ref "C2") (pin "2") (pinfunction "2_2") (pintype "passive"))
      (node (ref "U1") (pin "71") (pinfunction "VCAP_1_71") (pintype "power_in"))
    )
    (net (code "120") (name "/VCAP2") (class "Default")
      (node (ref "C1") (pin "2") (pinfunction "2_2") (pintype "passive"))
      (node (ref "U1") (pin "106") (pinfunction "VCAP_2_106") (pintype "power_in"))
    )
    (net (code "121") (name "GND") (class "Default")
      (node (ref "BT1") (pin "2") (pinfunction "-_2") (pintype "passive"))
      (node (ref "C1") (pin "1") (pinfunction "1_1") (pintype "passive"))
      (node (ref "C10") (pin "2") (pinfunction "2_2") (pintype "passive"))
      (node (ref "C11") (pin "2") (pinfunction "2_2") (pintype "passive"))
      (node (ref "C2") (pin "1") (pinfunction "1_1") (pintype "passive"))
      (node (ref "C3") (pin "2") (pinfunction "2_2") (pintype "passive"))
      (node (ref "C4") (pin "2") (pinfunction "2_2") (pintype "passive"))
      (node (ref "C5") (pin "2") (pinfunction "2_2") (pintype "passive"))
      (node (ref "C6") (pin "2") (pinfunction "2_2") (pintype "passive"))
      (node (ref "C8") (pin "1") (pinfunction "1_1") (pintype "passive"))
      (node (ref "C9") (pin "1") (pinfunction "1_1") (pintype "passive"))
      (node (ref "D3") (pin "2") (pinfunction "A_2") (pintype "passive"))
      (node (ref "D4") (pin "2") (pinfunction "A_2") (pintype "passive"))
      (node (ref "IO") (pin "2") (pinfunction "K_2") (pintype "passive"))
      (node (ref "KEY_A") (pin "2") (pinfunction "2_2") (pintype "passive"))
      (node (ref "KEY_B") (pin "2") (pinfunction "2_2") (pintype "passive"))
      (node (ref "LCD") (pin "22") (pinfunction "GND_22") (pintype "passive"))
      (node (ref "LCD") (pin "26") (pinfunction "GND_26") (pintype "passive"))
      (node (ref "LCD") (pin "27") (pinfunction "GND_27") (pintype "passive"))
      (node (ref "ON") (pin "2") (pinfunction "K_2") (pintype "passive"))
      (node (ref "Power_IN") (pin "2") (pinfunction "2_2") (pintype "passive"))
      (node (ref "Q2") (pin "2") (pinfunction "E_2") (pintype "passive"))
      (node (ref "R24") (pin "1") (pinfunction "1_1") (pintype "passive"))
      (node (ref "R3") (pin "1") (pinfunction "1_1") (pintype "passive"))
      (node (ref "R5") (pin "1") (pinfunction "1_1") (pintype "passive"))
      (node (ref "R6") (pin "2") (pinfunction "2_2") (pintype "passive"))
      (node (ref "R8") (pin "2") (pinfunction "2_2") (pintype "passive"))
      (node (ref "RESET") (pin "2") (pinfunction "2_2") (pintype "passive"))
      (node (ref "U1") (pin "107") (pinfunction "VSS_107") (pintype "power_in"))
      (node (ref "U1") (pin "120") (pinfunction "VSS_120") (pintype "power_in"))
      (node (ref "U1") (pin "130") (pinfunction "VSS_130") (pintype "power_in"))
      (node (ref "U1") (pin "16") (pinfunction "VSS_16") (pintype "power_in"))
      (node (ref "U1") (pin "38") (pinfunction "VSS_38") (pintype "power_in"))
      (node (ref "U1") (pin "51") (pinfunction "VSS_51") (pintype "power_in"))
      (node (ref "U1") (pin "61") (pinfunction "VSS_61") (pintype "power_in"))
      (node (ref "U1") (pin "83") (pinfunction "VSS_83") (pintype "power_in"))
      (node (ref "U1") (pin "94") (pinfunction "VSS_94") (pintype "power_in"))
      (node (ref "U2") (pin "12") (pinfunction "GND_12") (pintype "power_in"))
      (node (ref "U2") (pin "34") (pinfunction "GND_34") (pintype "power_in"))
      (node (ref "U3") (pin "1") (pinfunction "GND_1") (pintype "power_in"))
    )
    (net (code "122") (name "Net-(BT1-+)") (class "Default")
      (node (ref "BT1") (pin "1") (pinfunction "+_1") (pintype "passive"))
      (node (ref "D1") (pin "2") (pinfunction "A_2") (pintype "passive"))
    )
    (net (code "123") (name "Net-(C8-Pad2)") (class "Default")
      (node (ref "C8") (pin "2") (pinfunction "2_2") (pintype "passive"))
      (node (ref "R21") (pin "2") (pinfunction "2_2") (pintype "passive"))
      (node (ref "R22") (pin "1") (pinfunction "1_1") (pintype "passive"))
    )
    (net (code "124") (name "Net-(D1-K)") (class "Default")
      (node (ref "C5") (pin "1") (pinfunction "1_1") (pintype "passive"))
      (node (ref "D1") (pin "1") (pinfunction "K_1") (pintype "passive"))
      (node (ref "D2") (pin "1") (pinfunction "K_1") (pintype "passive"))
      (node (ref "U1") (pin "6") (pinfunction "VBAT_6") (pintype "power_in"))
    )
    (net (code "125") (name "Net-(IO-A)") (class "Default")
      (node (ref "IO") (pin "1") (pinfunction "A_1") (pintype "passive"))
      (node (ref "R26") (pin "1") (pinfunction "1_1") (pintype "passive"))
    )
    (net (code "126") (name "Net-(ON-A)") (class "Default")
      (node (ref "ON") (pin "1") (pinfunction "A_1") (pintype "passive"))
      (node (ref "R25") (pin "1") (pinfunction "1_1") (pintype "passive"))
    )
    (net (code "127") (name "Net-(Q2-B)") (class "Default")
      (node (ref "Q2") (pin "1") (pinfunction "B_1") (pintype "passive"))
      (node (ref "R23") (pin "2") (pinfunction "2_2") (pintype "passive"))
      (node (ref "R24") (pin "2") (pinfunction "2_2") (pintype "passive"))
    )
    (net (code "128") (name "Net-(Q2-C)") (class "Default")
      (node (ref "LS1") (pin "2") (pinfunction "2_2") (pintype "passive"))
      (node (ref "Q2") (pin "3") (pinfunction "C_3") (pintype "passive"))
    )
    (net (code "129") (name "Net-(U1C-VREF+)") (class "Default")
      (node (ref "R1") (pin "1") (pinfunction "1_1") (pintype "passive"))
      (node (ref "R3") (pin "2") (pinfunction "2_2") (pintype "passive"))
      (node (ref "U1") (pin "32") (pinfunction "VREF+_32") (pintype "power_in"))
    )
    (net (code "130") (name "PF10") (class "Default")
      (node (ref "R26") (pin "2") (pinfunction "2_2") (pintype "passive"))
      (node (ref "U1") (pin "22") (pinfunction "PF10_22") (pintype "bidirectional"))
    )
    (net (code "131") (name "VCC") (class "Default")
      (node (ref "D2") (pin "2") (pinfunction "A_2") (pintype "passive"))
      (node (ref "D4") (pin "1") (pinfunction "K_1") (pintype "passive"))
      (node (ref "LCD") (pin "24") (pinfunction "VDD3.3_24") (pintype "passive"))
      (node (ref "LCD") (pin "25") (pinfunction "VDD3.3_25") (pintype "passive"))
      (node (ref "LS1") (pin "1") (pinfunction "1_1") (pintype "passive"))
      (node (ref "R25") (pin "2") (pinfunction "2_2") (pintype "passive"))
      (node (ref "R4") (pin "1") (pinfunction "1_1") (pintype "passive"))
      (node (ref "R7") (pin "2") (pinfunction "2_2") (pintype "passive"))
      (node (ref "R9") (pin "2") (pinfunction "2_2") (pintype "passive"))
      (node (ref "U1") (pin "108") (pinfunction "VDD_108") (pintype "power_in"))
      (node (ref "U1") (pin "121") (pinfunction "VDD_121") (pintype "power_in"))
      (node (ref "U1") (pin "131") (pinfunction "VDD_131") (pintype "power_in"))
      (node (ref "U1") (pin "144") (pinfunction "VDD_144") (pintype "power_in"))
      (node (ref "U1") (pin "17") (pinfunction "VDD_17") (pintype "power_in"))
      (node (ref "U1") (pin "30") (pinfunction "VDD_30") (pintype "power_in"))
      (node (ref "U1") (pin "39") (pinfunction "VDD_39") (pintype "power_in"))
      (node (ref "U1") (pin "52") (pinfunction "VDD_52") (pintype "power_in"))
      (node (ref "U1") (pin "62") (pinfunction "VDD_62") (pintype "power_in"))
      (node (ref "U1") (pin "72") (pinfunction "VDD_72") (pintype "power_in"))
      (node (ref "U1") (pin "84") (pinfunction "VDD_84") (pintype "power_in"))
      (node (ref "U1") (pin "95") (pinfunction "VDD_95") (pintype "power_in"))
      (node (ref "U2") (pin "11") (pinfunction "VDD_11") (pintype "power_in"))
      (node (ref "U2") (pin "33") (pinfunction "VDD_33") (pintype "power_in"))
      (node (ref "U3") (pin "2") (pinfunction "VOUT_2") (pintype "power_in"))
    )
    (net (code "132") (name "VCCA") (class "Default")
      (node (ref "C7") (pin "2") (pinfunction "2_2") (pintype "passive"))
      (node (ref "R1") (pin "2") (pinfunction "2_2") (pintype "passive"))
      (node (ref "R7") (pin "1") (pinfunction "1_1") (pintype "passive"))
      (node (ref "U1") (pin "33") (pinfunction "VDDA_33") (pintype "power_in"))
    )
    (net (code "133") (name "VSSA") (class "Default")
      (node (ref "C7") (pin "1") (pinfunction "1_1") (pintype "passive"))
      (node (ref "R8") (pin "1") (pinfunction "1_1") (pintype "passive"))
      (node (ref "U1") (pin "31") (pinfunction "VSSA_31") (pintype "power_in"))
    )
    (net (code "134") (name "unconnected-(LCD-MO-Pad32)") (class "Default")
      (node (ref "LCD") (pin "32") (pinfunction "MO_32") (pintype "passive"))
    )
  )
)
